# PowerManagementBoard.net
KiCad netlist of a schematic drawn in EAGLE
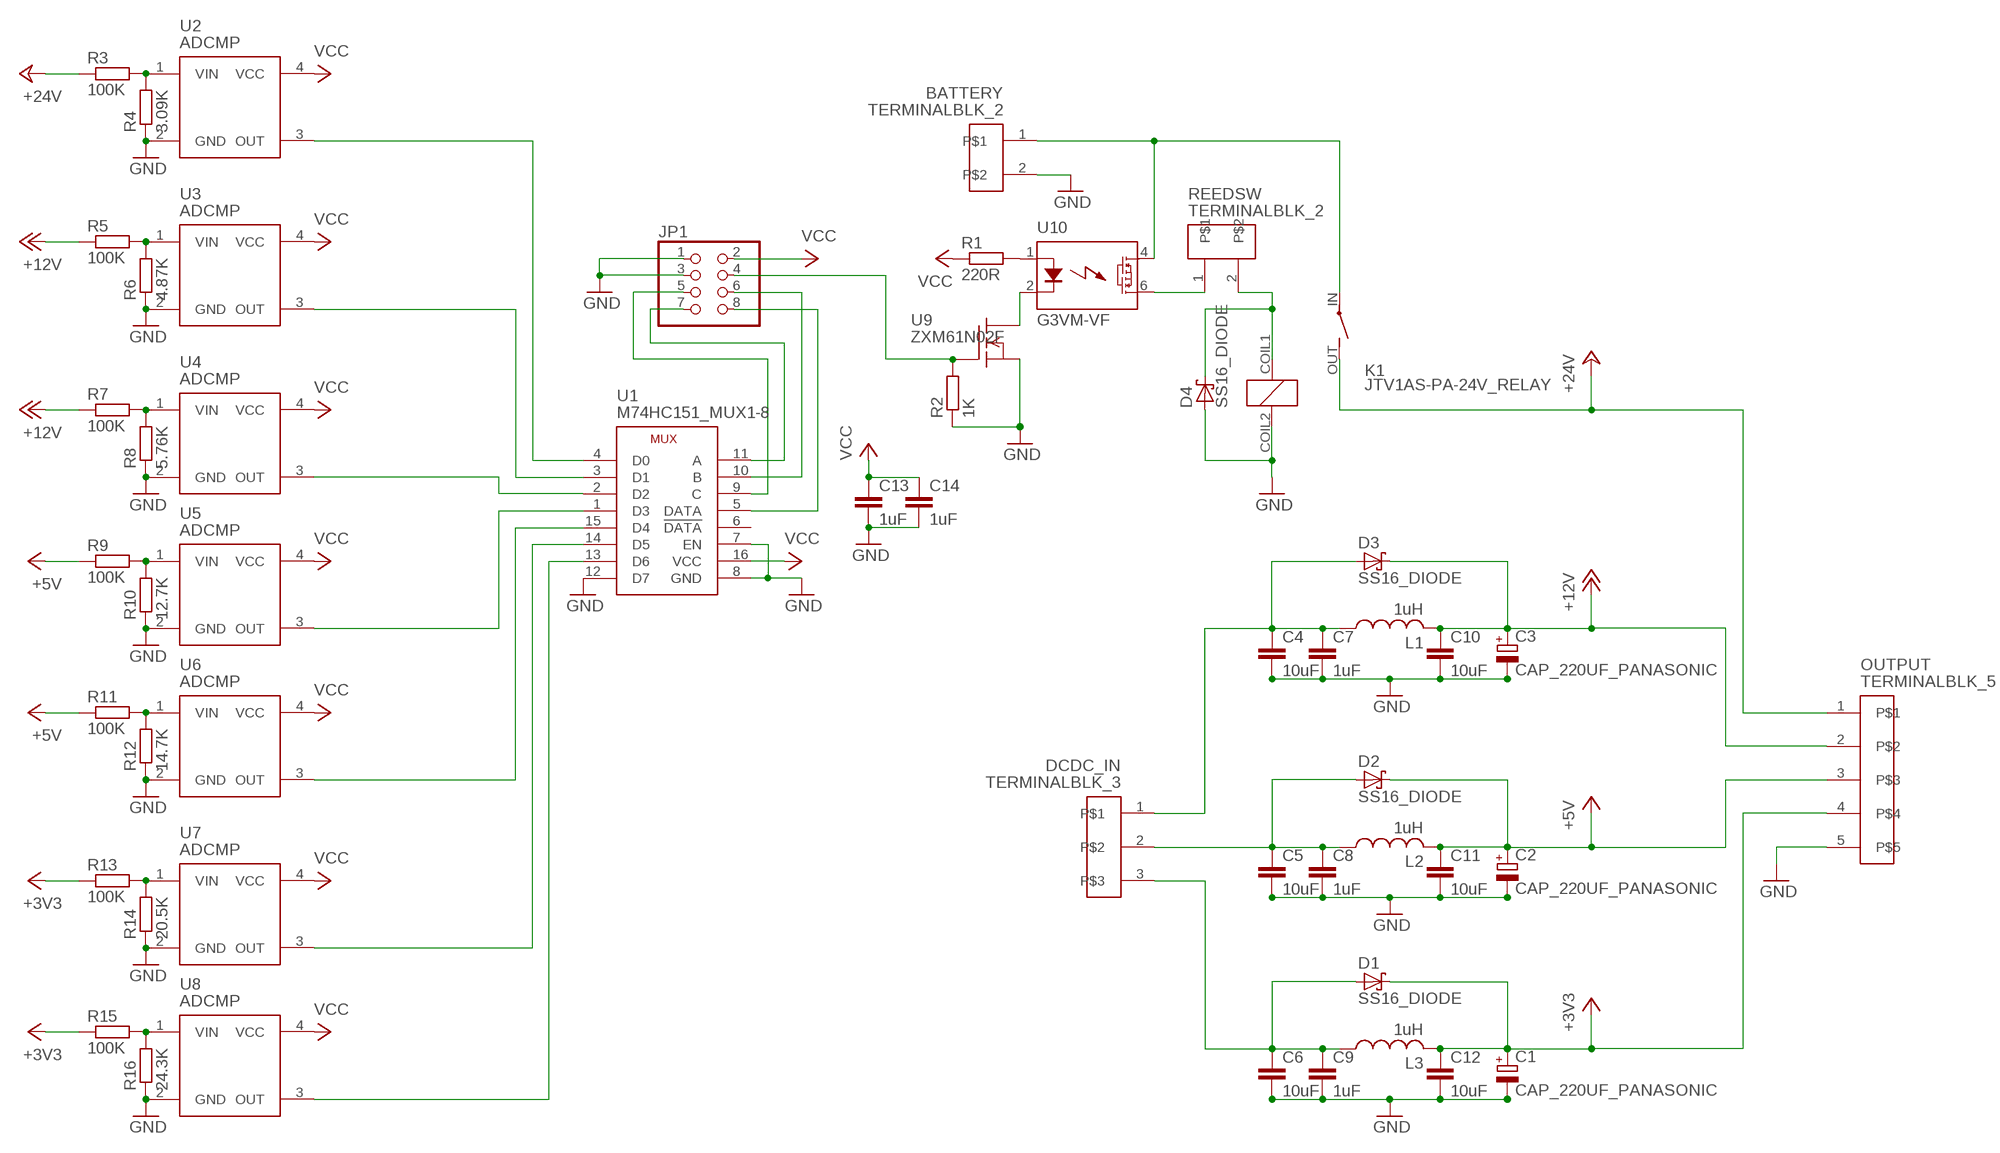
[diagram p0: schematic, sheet 1]

(export (version "E")
  (design (tool "Eeschema 10.0.6"))
  (components
    (comp (ref "BATTERY")
      (value "TERMINALBLK_2")
      (footprint "eagle-import:TERMINAL_BLK-2")
      (libsource (lib "eagle-import") (part "TERMINALBLK_2"))
    )
    (comp (ref "C1")
      (value "CAP_220UF_PANASONIC")
      (footprint "eagle-import:CAP_220UF_PANASONIC")
      (libsource (lib "eagle-import") (part "CAP_220UF_PANASONIC"))
    )
    (comp (ref "C2")
      (value "CAP_220UF_PANASONIC")
      (footprint "eagle-import:CAP_220UF_PANASONIC")
      (libsource (lib "eagle-import") (part "CAP_220UF_PANASONIC"))
    )
    (comp (ref "C3")
      (value "CAP_220UF_PANASONIC")
      (footprint "eagle-import:CAP_220UF_PANASONIC")
      (libsource (lib "eagle-import") (part "CAP_220UF_PANASONIC"))
    )
    (comp (ref "C4")
      (value "10uF")
      (footprint "eagle-import:C1206")
      (libsource (lib "eagle-import") (part "C-EUC1206"))
    )
    (comp (ref "C5")
      (value "10uF")
      (footprint "eagle-import:C1206")
      (libsource (lib "eagle-import") (part "C-EUC1206"))
    )
    (comp (ref "C6")
      (value "10uF")
      (footprint "eagle-import:C1206")
      (libsource (lib "eagle-import") (part "C-EUC1206"))
    )
    (comp (ref "C7")
      (value "1uF")
      (footprint "eagle-import:C1206")
      (libsource (lib "eagle-import") (part "C-EUC1206"))
    )
    (comp (ref "C8")
      (value "1uF")
      (footprint "eagle-import:C1206")
      (libsource (lib "eagle-import") (part "C-EUC1206"))
    )
    (comp (ref "C9")
      (value "1uF")
      (footprint "eagle-import:C1206")
      (libsource (lib "eagle-import") (part "C-EUC1206"))
    )
    (comp (ref "C10")
      (value "10uF")
      (footprint "eagle-import:C1206")
      (libsource (lib "eagle-import") (part "C-EUC1206"))
    )
    (comp (ref "C11")
      (value "10uF")
      (footprint "eagle-import:C1206")
      (libsource (lib "eagle-import") (part "C-EUC1206"))
    )
    (comp (ref "C12")
      (value "10uF")
      (footprint "eagle-import:C1206")
      (libsource (lib "eagle-import") (part "C-EUC1206"))
    )
    (comp (ref "C13")
      (value "1uF")
      (footprint "eagle-import:C1206")
      (libsource (lib "eagle-import") (part "C-EUC1206"))
    )
    (comp (ref "C14")
      (value "1uF")
      (footprint "eagle-import:C1206")
      (libsource (lib "eagle-import") (part "C-EUC1206"))
    )
    (comp (ref "D1")
      (value "SS16_DIODE")
      (footprint "eagle-import:DO214AC")
      (libsource (lib "eagle-import") (part "SS16_DIODE"))
    )
    (comp (ref "D2")
      (value "SS16_DIODE")
      (footprint "eagle-import:DO214AC")
      (libsource (lib "eagle-import") (part "SS16_DIODE"))
    )
    (comp (ref "D3")
      (value "SS16_DIODE")
      (footprint "eagle-import:DO214AC")
      (libsource (lib "eagle-import") (part "SS16_DIODE"))
    )
    (comp (ref "D4")
      (value "SS16_DIODE")
      (footprint "eagle-import:DO214AC")
      (libsource (lib "eagle-import") (part "SS16_DIODE"))
    )
    (comp (ref "DCDC_IN")
      (value "TERMINALBLK_3")
      (footprint "eagle-import:TERMINAL_BLK-3")
      (libsource (lib "eagle-import") (part "TERMINALBLK_3"))
    )
    (comp (ref "JP1")
      (value "PINHD-2X4")
      (footprint "eagle-import:2X04")
      (libsource (lib "eagle-import") (part "PINHD-2X4"))
    )
    (comp (ref "K1")
      (value "JTV1AS-PA-24V_RELAY")
      (footprint "eagle-import:JTV-RELAY_FORM1A")
      (libsource (lib "eagle-import") (part "JTV1AS-PA-24V_RELAY"))
    )
    (comp (ref "L1")
      (value "1uH")
      (footprint "eagle-import:CHOKE_WE-HCC_8070")
      (libsource (lib "eagle-import") (part "CHOKE_1UH_WE-HCC_8070"))
    )
    (comp (ref "L2")
      (value "1uH")
      (footprint "eagle-import:CHOKE_WE-HCC_8070")
      (libsource (lib "eagle-import") (part "CHOKE_1UH_WE-HCC_8070"))
    )
    (comp (ref "L3")
      (value "1uH")
      (footprint "eagle-import:CHOKE_WE-HCC_8070")
      (libsource (lib "eagle-import") (part "CHOKE_1UH_WE-HCC_8070"))
    )
    (comp (ref "OUTPUT")
      (value "TERMINALBLK_5")
      (footprint "eagle-import:TERMINAL_BLK-5")
      (libsource (lib "eagle-import") (part "TERMINALBLK_5"))
    )
    (comp (ref "R1")
      (value "220R")
      (footprint "eagle-import:R0603")
      (libsource (lib "eagle-import") (part "R-EU_R0603"))
    )
    (comp (ref "R2")
      (value "1K")
      (footprint "eagle-import:R0603")
      (libsource (lib "eagle-import") (part "R-EU_R0603"))
    )
    (comp (ref "R3")
      (value "100K")
      (footprint "eagle-import:R0603")
      (libsource (lib "eagle-import") (part "R-EU_R0603"))
    )
    (comp (ref "R4")
      (value "3.09K")
      (footprint "eagle-import:R0603")
      (libsource (lib "eagle-import") (part "R-EU_R0603"))
    )
    (comp (ref "R5")
      (value "100K")
      (footprint "eagle-import:R0603")
      (libsource (lib "eagle-import") (part "R-EU_R0603"))
    )
    (comp (ref "R6")
      (value "4.87K")
      (footprint "eagle-import:R0603")
      (libsource (lib "eagle-import") (part "R-EU_R0603"))
    )
    (comp (ref "R7")
      (value "100K")
      (footprint "eagle-import:R0603")
      (libsource (lib "eagle-import") (part "R-EU_R0603"))
    )
    (comp (ref "R8")
      (value "5.76K")
      (footprint "eagle-import:R0603")
      (libsource (lib "eagle-import") (part "R-EU_R0603"))
    )
    (comp (ref "R9")
      (value "100K")
      (footprint "eagle-import:R0603")
      (libsource (lib "eagle-import") (part "R-EU_R0603"))
    )
    (comp (ref "R10")
      (value "12.7K")
      (footprint "eagle-import:R0603")
      (libsource (lib "eagle-import") (part "R-EU_R0603"))
    )
    (comp (ref "R11")
      (value "100K")
      (footprint "eagle-import:R0603")
      (libsource (lib "eagle-import") (part "R-EU_R0603"))
    )
    (comp (ref "R12")
      (value "14.7K")
      (footprint "eagle-import:R0603")
      (libsource (lib "eagle-import") (part "R-EU_R0603"))
    )
    (comp (ref "R13")
      (value "100K")
      (footprint "eagle-import:R0603")
      (libsource (lib "eagle-import") (part "R-EU_R0603"))
    )
    (comp (ref "R14")
      (value "20.5K")
      (footprint "eagle-import:R0603")
      (libsource (lib "eagle-import") (part "R-EU_R0603"))
    )
    (comp (ref "R15")
      (value "100K")
      (footprint "eagle-import:R0603")
      (libsource (lib "eagle-import") (part "R-EU_R0603"))
    )
    (comp (ref "R16")
      (value "24.3K")
      (footprint "eagle-import:R0603")
      (libsource (lib "eagle-import") (part "R-EU_R0603"))
    )
    (comp (ref "REEDSW")
      (value "TERMINALBLK_2")
      (footprint "eagle-import:TERMINAL_BLK-2")
      (libsource (lib "eagle-import") (part "TERMINALBLK_2"))
    )
    (comp (ref "U1")
      (value "M74HC151_MUX1-8")
      (footprint "eagle-import:TSSOP16")
      (libsource (lib "eagle-import") (part "M74HC151_MUX1-8"))
    )
    (comp (ref "U2")
      (value "ADCMP")
      (footprint "eagle-import:SC70-4")
      (libsource (lib "eagle-import") (part "ADCMP"))
    )
    (comp (ref "U3")
      (value "ADCMP")
      (footprint "eagle-import:SC70-4")
      (libsource (lib "eagle-import") (part "ADCMP"))
    )
    (comp (ref "U4")
      (value "ADCMP")
      (footprint "eagle-import:SC70-4")
      (libsource (lib "eagle-import") (part "ADCMP"))
    )
    (comp (ref "U5")
      (value "ADCMP")
      (footprint "eagle-import:SC70-4")
      (libsource (lib "eagle-import") (part "ADCMP"))
    )
    (comp (ref "U6")
      (value "ADCMP")
      (footprint "eagle-import:SC70-4")
      (libsource (lib "eagle-import") (part "ADCMP"))
    )
    (comp (ref "U7")
      (value "ADCMP")
      (footprint "eagle-import:SC70-4")
      (libsource (lib "eagle-import") (part "ADCMP"))
    )
    (comp (ref "U8")
      (value "ADCMP")
      (footprint "eagle-import:SC70-4")
      (libsource (lib "eagle-import") (part "ADCMP"))
    )
    (comp (ref "U9")
      (value "ZXM61N02F")
      (footprint "eagle-import:SOT23W")
      (libsource (lib "eagle-import") (part "ZXM61N02F"))
    )
    (comp (ref "U10")
      (value "G3VM-VF")
      (footprint "eagle-import:G3VM-VF")
      (libsource (lib "eagle-import") (part "G3VM-VF"))
    )
  )
  (nets
    (net (code "1") (name "+3V3") (class "Default")
      (node (ref "C1") (pin "P") (pinfunction "+_P") (pintype "passive"))
      (node (ref "C12") (pin "1") (pinfunction "1_1") (pintype "passive"))
      (node (ref "D1") (pin "C") (pinfunction "C_C") (pintype "passive"))
      (node (ref "L3") (pin "P$2") (pinfunction "2_P$2") (pintype "passive"))
      (node (ref "OUTPUT") (pin "4") (pinfunction "P$4_4") (pintype "bidirectional"))
      (node (ref "R13") (pin "1") (pinfunction "1_1") (pintype "passive"))
      (node (ref "R15") (pin "1") (pinfunction "1_1") (pintype "passive"))
    )
    (net (code "2") (name "+5V") (class "Default")
      (node (ref "C11") (pin "1") (pinfunction "1_1") (pintype "passive"))
      (node (ref "C2") (pin "P") (pinfunction "+_P") (pintype "passive"))
      (node (ref "D2") (pin "C") (pinfunction "C_C") (pintype "passive"))
      (node (ref "L2") (pin "P$2") (pinfunction "2_P$2") (pintype "passive"))
      (node (ref "OUTPUT") (pin "3") (pinfunction "P$3_3") (pintype "bidirectional"))
      (node (ref "R11") (pin "1") (pinfunction "1_1") (pintype "passive"))
      (node (ref "R9") (pin "1") (pinfunction "1_1") (pintype "passive"))
    )
    (net (code "3") (name "+12V") (class "Default")
      (node (ref "C10") (pin "1") (pinfunction "1_1") (pintype "passive"))
      (node (ref "C3") (pin "P") (pinfunction "+_P") (pintype "passive"))
      (node (ref "D3") (pin "C") (pinfunction "C_C") (pintype "passive"))
      (node (ref "L1") (pin "P$2") (pinfunction "2_P$2") (pintype "passive"))
      (node (ref "OUTPUT") (pin "2") (pinfunction "P$2_2") (pintype "bidirectional"))
      (node (ref "R5") (pin "1") (pinfunction "1_1") (pintype "passive"))
      (node (ref "R7") (pin "1") (pinfunction "1_1") (pintype "passive"))
    )
    (net (code "4") (name "+24V") (class "Default")
      (node (ref "K1") (pin "OUT") (pinfunction "S_OUT") (pintype "passive"))
      (node (ref "OUTPUT") (pin "1") (pinfunction "P$1_1") (pintype "bidirectional"))
      (node (ref "R3") (pin "1") (pinfunction "1_1") (pintype "passive"))
    )
    (net (code "5") (name "GND") (class "Default")
      (node (ref "BATTERY") (pin "2") (pinfunction "P$2_2") (pintype "bidirectional"))
      (node (ref "C1") (pin "N") (pinfunction "-_N") (pintype "passive"))
      (node (ref "C10") (pin "2") (pinfunction "2_2") (pintype "passive"))
      (node (ref "C11") (pin "2") (pinfunction "2_2") (pintype "passive"))
      (node (ref "C12") (pin "2") (pinfunction "2_2") (pintype "passive"))
      (node (ref "C13") (pin "2") (pinfunction "2_2") (pintype "passive"))
      (node (ref "C14") (pin "2") (pinfunction "2_2") (pintype "passive"))
      (node (ref "C2") (pin "N") (pinfunction "-_N") (pintype "passive"))
      (node (ref "C3") (pin "N") (pinfunction "-_N") (pintype "passive"))
      (node (ref "C4") (pin "2") (pinfunction "2_2") (pintype "passive"))
      (node (ref "C5") (pin "2") (pinfunction "2_2") (pintype "passive"))
      (node (ref "C6") (pin "2") (pinfunction "2_2") (pintype "passive"))
      (node (ref "C7") (pin "2") (pinfunction "2_2") (pintype "passive"))
      (node (ref "C8") (pin "2") (pinfunction "2_2") (pintype "passive"))
      (node (ref "C9") (pin "2") (pinfunction "2_2") (pintype "passive"))
      (node (ref "D4") (pin "A") (pinfunction "A_A") (pintype "passive"))
      (node (ref "JP1") (pin "1") (pinfunction "1_1") (pintype "passive"))
      (node (ref "JP1") (pin "3") (pinfunction "3_3") (pintype "passive"))
      (node (ref "K1") (pin "COIL2") (pinfunction "2_COIL2") (pintype "passive"))
      (node (ref "OUTPUT") (pin "5") (pinfunction "P$5_5") (pintype "bidirectional"))
      (node (ref "R10") (pin "1") (pinfunction "1_1") (pintype "passive"))
      (node (ref "R12") (pin "1") (pinfunction "1_1") (pintype "passive"))
      (node (ref "R14") (pin "1") (pinfunction "1_1") (pintype "passive"))
      (node (ref "R16") (pin "1") (pinfunction "1_1") (pintype "passive"))
      (node (ref "R2") (pin "1") (pinfunction "1_1") (pintype "passive"))
      (node (ref "R4") (pin "1") (pinfunction "1_1") (pintype "passive"))
      (node (ref "R6") (pin "1") (pinfunction "1_1") (pintype "passive"))
      (node (ref "R8") (pin "1") (pinfunction "1_1") (pintype "passive"))
      (node (ref "U1") (pin "12") (pinfunction "D7_12") (pintype "bidirectional"))
      (node (ref "U1") (pin "7") (pinfunction "EN_7") (pintype "bidirectional"))
      (node (ref "U1") (pin "8") (pinfunction "GND_8") (pintype "bidirectional"))
      (node (ref "U2") (pin "2") (pinfunction "GND_2") (pintype "bidirectional"))
      (node (ref "U3") (pin "2") (pinfunction "GND_2") (pintype "bidirectional"))
      (node (ref "U4") (pin "2") (pinfunction "GND_2") (pintype "bidirectional"))
      (node (ref "U5") (pin "2") (pinfunction "GND_2") (pintype "bidirectional"))
      (node (ref "U6") (pin "2") (pinfunction "GND_2") (pintype "bidirectional"))
      (node (ref "U7") (pin "2") (pinfunction "GND_2") (pintype "bidirectional"))
      (node (ref "U8") (pin "2") (pinfunction "GND_2") (pintype "bidirectional"))
      (node (ref "U9") (pin "2") (pinfunction "S_2") (pintype "passive"))
    )
    (net (code "6") (name "Net-(BATTERY-P$1)") (class "Default")
      (node (ref "BATTERY") (pin "1") (pinfunction "P$1_1") (pintype "bidirectional"))
      (node (ref "K1") (pin "IN") (pinfunction "P_IN") (pintype "passive"))
      (node (ref "U10") (pin "4") (pinfunction "DS1_4") (pintype "passive"))
    )
    (net (code "7") (name "Net-(DCDC_IN-P$1)") (class "Default")
      (node (ref "C4") (pin "1") (pinfunction "1_1") (pintype "passive"))
      (node (ref "C7") (pin "1") (pinfunction "1_1") (pintype "passive"))
      (node (ref "D3") (pin "A") (pinfunction "A_A") (pintype "passive"))
      (node (ref "DCDC_IN") (pin "1") (pinfunction "P$1_1") (pintype "bidirectional"))
      (node (ref "L1") (pin "P$1") (pinfunction "1_P$1") (pintype "passive"))
    )
    (net (code "8") (name "Net-(DCDC_IN-P$2)") (class "Default")
      (node (ref "C5") (pin "1") (pinfunction "1_1") (pintype "passive"))
      (node (ref "C8") (pin "1") (pinfunction "1_1") (pintype "passive"))
      (node (ref "D2") (pin "A") (pinfunction "A_A") (pintype "passive"))
      (node (ref "DCDC_IN") (pin "2") (pinfunction "P$2_2") (pintype "bidirectional"))
      (node (ref "L2") (pin "P$1") (pinfunction "1_P$1") (pintype "passive"))
    )
    (net (code "9") (name "Net-(DCDC_IN-P$3)") (class "Default")
      (node (ref "C6") (pin "1") (pinfunction "1_1") (pintype "passive"))
      (node (ref "C9") (pin "1") (pinfunction "1_1") (pintype "passive"))
      (node (ref "D1") (pin "A") (pinfunction "A_A") (pintype "passive"))
      (node (ref "DCDC_IN") (pin "3") (pinfunction "P$3_3") (pintype "bidirectional"))
      (node (ref "L3") (pin "P$1") (pinfunction "1_P$1") (pintype "passive"))
    )
    (net (code "10") (name "Net-(K1A-1)") (class "Default")
      (node (ref "D4") (pin "C") (pinfunction "C_C") (pintype "passive"))
      (node (ref "K1") (pin "COIL1") (pinfunction "1_COIL1") (pintype "passive"))
      (node (ref "REEDSW") (pin "2") (pinfunction "P$2_2") (pintype "bidirectional"))
    )
    (net (code "11") (name "Net-(REEDSW-P$1)") (class "Default")
      (node (ref "REEDSW") (pin "1") (pinfunction "P$1_1") (pintype "bidirectional"))
      (node (ref "U10") (pin "6") (pinfunction "DS2_6") (pintype "passive"))
    )
    (net (code "12") (name "Net-(U1-A)") (class "Default")
      (node (ref "JP1") (pin "7") (pinfunction "7_7") (pintype "passive"))
      (node (ref "U1") (pin "11") (pinfunction "A_11") (pintype "bidirectional"))
    )
    (net (code "13") (name "Net-(U1-B)") (class "Default")
      (node (ref "JP1") (pin "6") (pinfunction "6_6") (pintype "passive"))
      (node (ref "U1") (pin "10") (pinfunction "B_10") (pintype "bidirectional"))
    )
    (net (code "14") (name "Net-(U1-C)") (class "Default")
      (node (ref "JP1") (pin "5") (pinfunction "5_5") (pintype "passive"))
      (node (ref "U1") (pin "9") (pinfunction "C_9") (pintype "bidirectional"))
    )
    (net (code "15") (name "Net-(U1-D0)") (class "Default")
      (node (ref "U1") (pin "4") (pinfunction "D0_4") (pintype "bidirectional"))
      (node (ref "U2") (pin "3") (pinfunction "OUT_3") (pintype "bidirectional"))
    )
    (net (code "16") (name "Net-(U1-D1)") (class "Default")
      (node (ref "U1") (pin "3") (pinfunction "D1_3") (pintype "bidirectional"))
      (node (ref "U3") (pin "3") (pinfunction "OUT_3") (pintype "bidirectional"))
    )
    (net (code "17") (name "Net-(U1-D2)") (class "Default")
      (node (ref "U1") (pin "2") (pinfunction "D2_2") (pintype "bidirectional"))
      (node (ref "U4") (pin "3") (pinfunction "OUT_3") (pintype "bidirectional"))
    )
    (net (code "18") (name "Net-(U1-D3)") (class "Default")
      (node (ref "U1") (pin "1") (pinfunction "D3_1") (pintype "bidirectional"))
      (node (ref "U5") (pin "3") (pinfunction "OUT_3") (pintype "bidirectional"))
    )
    (net (code "19") (name "Net-(U1-D4)") (class "Default")
      (node (ref "U1") (pin "15") (pinfunction "D4_15") (pintype "bidirectional"))
      (node (ref "U6") (pin "3") (pinfunction "OUT_3") (pintype "bidirectional"))
    )
    (net (code "20") (name "Net-(U1-D5)") (class "Default")
      (node (ref "U1") (pin "14") (pinfunction "D5_14") (pintype "bidirectional"))
      (node (ref "U7") (pin "3") (pinfunction "OUT_3") (pintype "bidirectional"))
    )
    (net (code "21") (name "Net-(U1-D6)") (class "Default")
      (node (ref "U1") (pin "13") (pinfunction "D6_13") (pintype "bidirectional"))
      (node (ref "U8") (pin "3") (pinfunction "OUT_3") (pintype "bidirectional"))
    )
    (net (code "22") (name "Net-(U1-DATA)") (class "Default")
      (node (ref "JP1") (pin "8") (pinfunction "8_8") (pintype "passive"))
      (node (ref "U1") (pin "5") (pinfunction "DATA_5") (pintype "bidirectional"))
    )
    (net (code "23") (name "Net-(U2-VIN)") (class "Default")
      (node (ref "R3") (pin "2") (pinfunction "2_2") (pintype "passive"))
      (node (ref "R4") (pin "2") (pinfunction "2_2") (pintype "passive"))
      (node (ref "U2") (pin "1") (pinfunction "VIN_1") (pintype "bidirectional"))
    )
    (net (code "24") (name "Net-(U3-VIN)") (class "Default")
      (node (ref "R5") (pin "2") (pinfunction "2_2") (pintype "passive"))
      (node (ref "R6") (pin "2") (pinfunction "2_2") (pintype "passive"))
      (node (ref "U3") (pin "1") (pinfunction "VIN_1") (pintype "bidirectional"))
    )
    (net (code "25") (name "Net-(U4-VIN)") (class "Default")
      (node (ref "R7") (pin "2") (pinfunction "2_2") (pintype "passive"))
      (node (ref "R8") (pin "2") (pinfunction "2_2") (pintype "passive"))
      (node (ref "U4") (pin "1") (pinfunction "VIN_1") (pintype "bidirectional"))
    )
    (net (code "26") (name "Net-(U5-VIN)") (class "Default")
      (node (ref "R10") (pin "2") (pinfunction "2_2") (pintype "passive"))
      (node (ref "R9") (pin "2") (pinfunction "2_2") (pintype "passive"))
      (node (ref "U5") (pin "1") (pinfunction "VIN_1") (pintype "bidirectional"))
    )
    (net (code "27") (name "Net-(U6-VIN)") (class "Default")
      (node (ref "R11") (pin "2") (pinfunction "2_2") (pintype "passive"))
      (node (ref "R12") (pin "2") (pinfunction "2_2") (pintype "passive"))
      (node (ref "U6") (pin "1") (pinfunction "VIN_1") (pintype "bidirectional"))
    )
    (net (code "28") (name "Net-(U7-VIN)") (class "Default")
      (node (ref "R13") (pin "2") (pinfunction "2_2") (pintype "passive"))
      (node (ref "R14") (pin "2") (pinfunction "2_2") (pintype "passive"))
      (node (ref "U7") (pin "1") (pinfunction "VIN_1") (pintype "bidirectional"))
    )
    (net (code "29") (name "Net-(U8-VIN)") (class "Default")
      (node (ref "R15") (pin "2") (pinfunction "2_2") (pintype "passive"))
      (node (ref "R16") (pin "2") (pinfunction "2_2") (pintype "passive"))
      (node (ref "U8") (pin "1") (pinfunction "VIN_1") (pintype "bidirectional"))
    )
    (net (code "30") (name "Net-(U9-G)") (class "Default")
      (node (ref "JP1") (pin "4") (pinfunction "4_4") (pintype "passive"))
      (node (ref "R2") (pin "2") (pinfunction "2_2") (pintype "passive"))
      (node (ref "U9") (pin "1") (pinfunction "G_1") (pintype "passive"))
    )
    (net (code "31") (name "Net-(U10-A)") (class "Default")
      (node (ref "R1") (pin "2") (pinfunction "2_2") (pintype "passive"))
      (node (ref "U10") (pin "1") (pinfunction "A_1") (pintype "passive"))
    )
    (net (code "32") (name "Net-(U10-K)") (class "Default")
      (node (ref "U10") (pin "2") (pinfunction "K_2") (pintype "passive"))
      (node (ref "U9") (pin "3") (pinfunction "D_3") (pintype "passive"))
    )
    (net (code "33") (name "VCC") (class "Default")
      (node (ref "C13") (pin "1") (pinfunction "1_1") (pintype "passive"))
      (node (ref "C14") (pin "1") (pinfunction "1_1") (pintype "passive"))
      (node (ref "JP1") (pin "2") (pinfunction "2_2") (pintype "passive"))
      (node (ref "R1") (pin "1") (pinfunction "1_1") (pintype "passive"))
      (node (ref "U1") (pin "16") (pinfunction "VCC_16") (pintype "bidirectional"))
      (node (ref "U2") (pin "4") (pinfunction "VCC_4") (pintype "bidirectional"))
      (node (ref "U3") (pin "4") (pinfunction "VCC_4") (pintype "bidirectional"))
      (node (ref "U4") (pin "4") (pinfunction "VCC_4") (pintype "bidirectional"))
      (node (ref "U5") (pin "4") (pinfunction "VCC_4") (pintype "bidirectional"))
      (node (ref "U6") (pin "4") (pinfunction "VCC_4") (pintype "bidirectional"))
      (node (ref "U7") (pin "4") (pinfunction "VCC_4") (pintype "bidirectional"))
      (node (ref "U8") (pin "4") (pinfunction "VCC_4") (pintype "bidirectional"))
    )
    (net (code "34") (name "unconnected-(U1-~{DATA}-Pad6)") (class "Default")
      (node (ref "U1") (pin "6") (pinfunction "~{DATA}_6") (pintype "bidirectional"))
    )
  )
)
